# Breakout.net
KiCad netlist of a schematic drawn in EAGLE
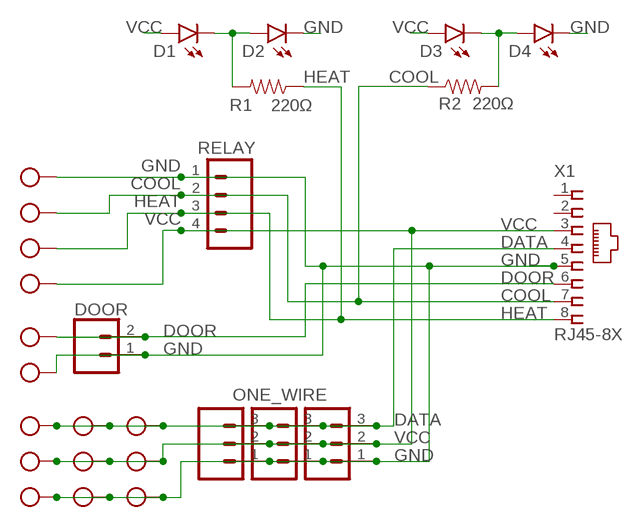
[diagram p0: schematic, sheet 1]

(export (version "E")
  (design (tool "Eeschema 10.0.6"))
  (components
    (comp (ref "D1")
      (value "HINV")
      (footprint "eagle-import:LED_3MM")
      (libsource (lib "eagle-import") (part "LED3MM"))
    )
    (comp (ref "D2")
      (value "HNON")
      (footprint "eagle-import:LED_3MM")
      (libsource (lib "eagle-import") (part "LED3MM"))
    )
    (comp (ref "D3")
      (value "CINV")
      (footprint "eagle-import:LED_3MM")
      (libsource (lib "eagle-import") (part "LED3MM"))
    )
    (comp (ref "D4")
      (value "CNON")
      (footprint "eagle-import:LED_3MM")
      (libsource (lib "eagle-import") (part "LED3MM"))
    )
    (comp (ref "DOOR")
      (value "2-PIN")
      (footprint "eagle-import:1X02")
      (libsource (lib "eagle-import") (part "CONN_02"))
    )
    (comp (ref "ONE_WIRE1")
      (value "3-PIN")
      (footprint "eagle-import:1X03")
      (libsource (lib "eagle-import") (part "CONN_03"))
    )
    (comp (ref "ONE_WIRE2")
      (value "3-PIN")
      (footprint "eagle-import:1X03")
      (libsource (lib "eagle-import") (part "CONN_03"))
    )
    (comp (ref "ONE_WIRE3")
      (value "3-PIN")
      (footprint "eagle-import:1X03")
      (libsource (lib "eagle-import") (part "CONN_03"))
    )
    (comp (ref "R1")
      (value "220Ω")
      (footprint "eagle-import:AXIAL-0.3")
      (libsource (lib "eagle-import") (part "RESISTORAXIAL-0.3"))
    )
    (comp (ref "R2")
      (value "220Ω")
      (footprint "eagle-import:AXIAL-0.3")
      (libsource (lib "eagle-import") (part "RESISTORAXIAL-0.3"))
    )
    (comp (ref "RELAY")
      (value "4-PIN")
      (footprint "eagle-import:1X04")
      (libsource (lib "eagle-import") (part "CONN_04PTH"))
    )
    (comp (ref "RELAY_TERM")
      (value "4TERM")
      (footprint "eagle-import:W237-4")
      (libsource (lib "eagle-import") (part "W237-4"))
    )
    (comp (ref "X1")
      (value "RJ45-8X")
      (footprint "eagle-import:RJ45-NO-SHIELD")
      (libsource (lib "eagle-import") (part "RJ45-8X"))
    )
    (comp (ref "X2")
      (value "4TERM")
      (footprint "eagle-import:W237-102")
      (fields (field (name "MPN") "237-102"))
      (libsource (lib "eagle-import") (part "W237-102"))
    )
    (comp (ref "X3")
      (value "3TERM")
      (footprint "eagle-import:W237-103")
      (fields (field (name "MPN") "237-103"))
      (libsource (lib "eagle-import") (part "W237-103"))
    )
    (comp (ref "X4")
      (value "3TERM")
      (footprint "eagle-import:W237-103")
      (fields (field (name "MPN") "237-103"))
      (libsource (lib "eagle-import") (part "W237-103"))
    )
    (comp (ref "X5")
      (value "3TERM")
      (footprint "eagle-import:W237-103")
      (fields (field (name "MPN") "237-103"))
      (libsource (lib "eagle-import") (part "W237-103"))
    )
  )
  (nets
    (net (code "1") (name "/COOL") (class "Default")
      (node (ref "R2") (pin "P$1") (pinfunction "1_P$1") (pintype "passive"))
      (node (ref "RELAY") (pin "2") (pinfunction "2_2") (pintype "passive"))
      (node (ref "RELAY_TERM") (pin "2") (pinfunction "KL_2") (pintype "passive"))
      (node (ref "X1") (pin "7") (pinfunction "7_7") (pintype "passive"))
    )
    (net (code "2") (name "/DATA") (class "Default")
      (node (ref "ONE_WIRE1") (pin "3") (pinfunction "3_3") (pintype "passive"))
      (node (ref "ONE_WIRE2") (pin "3") (pinfunction "3_3") (pintype "passive"))
      (node (ref "ONE_WIRE3") (pin "3") (pinfunction "3_3") (pintype "passive"))
      (node (ref "X1") (pin "4") (pinfunction "4_4") (pintype "passive"))
      (node (ref "X3") (pin "1") (pinfunction "KL_1") (pintype "passive"))
      (node (ref "X4") (pin "1") (pinfunction "KL_1") (pintype "passive"))
      (node (ref "X5") (pin "1") (pinfunction "KL_1") (pintype "passive"))
    )
    (net (code "3") (name "/DOOR") (class "Default")
      (node (ref "DOOR") (pin "2") (pinfunction "2_2") (pintype "passive"))
      (node (ref "X1") (pin "6") (pinfunction "6_6") (pintype "passive"))
      (node (ref "X2") (pin "1") (pinfunction "KL_1") (pintype "passive"))
    )
    (net (code "4") (name "/GND") (class "Default")
      (node (ref "D2") (pin "K") (pinfunction "C_K") (pintype "passive"))
      (node (ref "D4") (pin "K") (pinfunction "C_K") (pintype "passive"))
      (node (ref "DOOR") (pin "1") (pinfunction "1_1") (pintype "passive"))
      (node (ref "ONE_WIRE1") (pin "1") (pinfunction "1_1") (pintype "passive"))
      (node (ref "ONE_WIRE2") (pin "1") (pinfunction "1_1") (pintype "passive"))
      (node (ref "ONE_WIRE3") (pin "1") (pinfunction "1_1") (pintype "passive"))
      (node (ref "RELAY") (pin "1") (pinfunction "1_1") (pintype "passive"))
      (node (ref "RELAY_TERM") (pin "1") (pinfunction "KL_1") (pintype "passive"))
      (node (ref "X1") (pin "5") (pinfunction "5_5") (pintype "passive"))
      (node (ref "X2") (pin "2") (pinfunction "KL_2") (pintype "passive"))
      (node (ref "X3") (pin "3") (pinfunction "KL_3") (pintype "passive"))
      (node (ref "X4") (pin "3") (pinfunction "KL_3") (pintype "passive"))
      (node (ref "X5") (pin "3") (pinfunction "KL_3") (pintype "passive"))
    )
    (net (code "5") (name "/HEAT") (class "Default")
      (node (ref "R1") (pin "P$1") (pinfunction "1_P$1") (pintype "passive"))
      (node (ref "RELAY") (pin "3") (pinfunction "3_3") (pintype "passive"))
      (node (ref "RELAY_TERM") (pin "3") (pinfunction "KL_3") (pintype "passive"))
      (node (ref "X1") (pin "8") (pinfunction "8_8") (pintype "passive"))
    )
    (net (code "6") (name "/VCC") (class "Default")
      (node (ref "D1") (pin "A") (pinfunction "A_A") (pintype "passive"))
      (node (ref "D3") (pin "A") (pinfunction "A_A") (pintype "passive"))
      (node (ref "ONE_WIRE1") (pin "2") (pinfunction "2_2") (pintype "passive"))
      (node (ref "ONE_WIRE2") (pin "2") (pinfunction "2_2") (pintype "passive"))
      (node (ref "ONE_WIRE3") (pin "2") (pinfunction "2_2") (pintype "passive"))
      (node (ref "RELAY") (pin "4") (pinfunction "4_4") (pintype "passive"))
      (node (ref "RELAY_TERM") (pin "4") (pinfunction "KL_4") (pintype "passive"))
      (node (ref "X1") (pin "3") (pinfunction "3_3") (pintype "passive"))
      (node (ref "X3") (pin "2") (pinfunction "KL_2") (pintype "passive"))
      (node (ref "X4") (pin "2") (pinfunction "KL_2") (pintype "passive"))
      (node (ref "X5") (pin "2") (pinfunction "KL_2") (pintype "passive"))
    )
    (net (code "7") (name "Net-(D1-C)") (class "Default")
      (node (ref "D1") (pin "K") (pinfunction "C_K") (pintype "passive"))
      (node (ref "D2") (pin "A") (pinfunction "A_A") (pintype "passive"))
      (node (ref "R1") (pin "P$2") (pinfunction "2_P$2") (pintype "passive"))
    )
    (net (code "8") (name "Net-(D3-C)") (class "Default")
      (node (ref "D3") (pin "K") (pinfunction "C_K") (pintype "passive"))
      (node (ref "D4") (pin "A") (pinfunction "A_A") (pintype "passive"))
      (node (ref "R2") (pin "P$2") (pinfunction "2_P$2") (pintype "passive"))
    )
    (net (code "9") (name "unconnected-(X1-Pad1)") (class "Default")
      (node (ref "X1") (pin "1") (pinfunction "1_1") (pintype "passive"))
    )
    (net (code "10") (name "unconnected-(X1-Pad2)") (class "Default")
      (node (ref "X1") (pin "2") (pinfunction "2_2") (pintype "passive"))
    )
  )
)
